# 6-digit-board.net
KiCad netlist of a schematic drawn in EAGLE
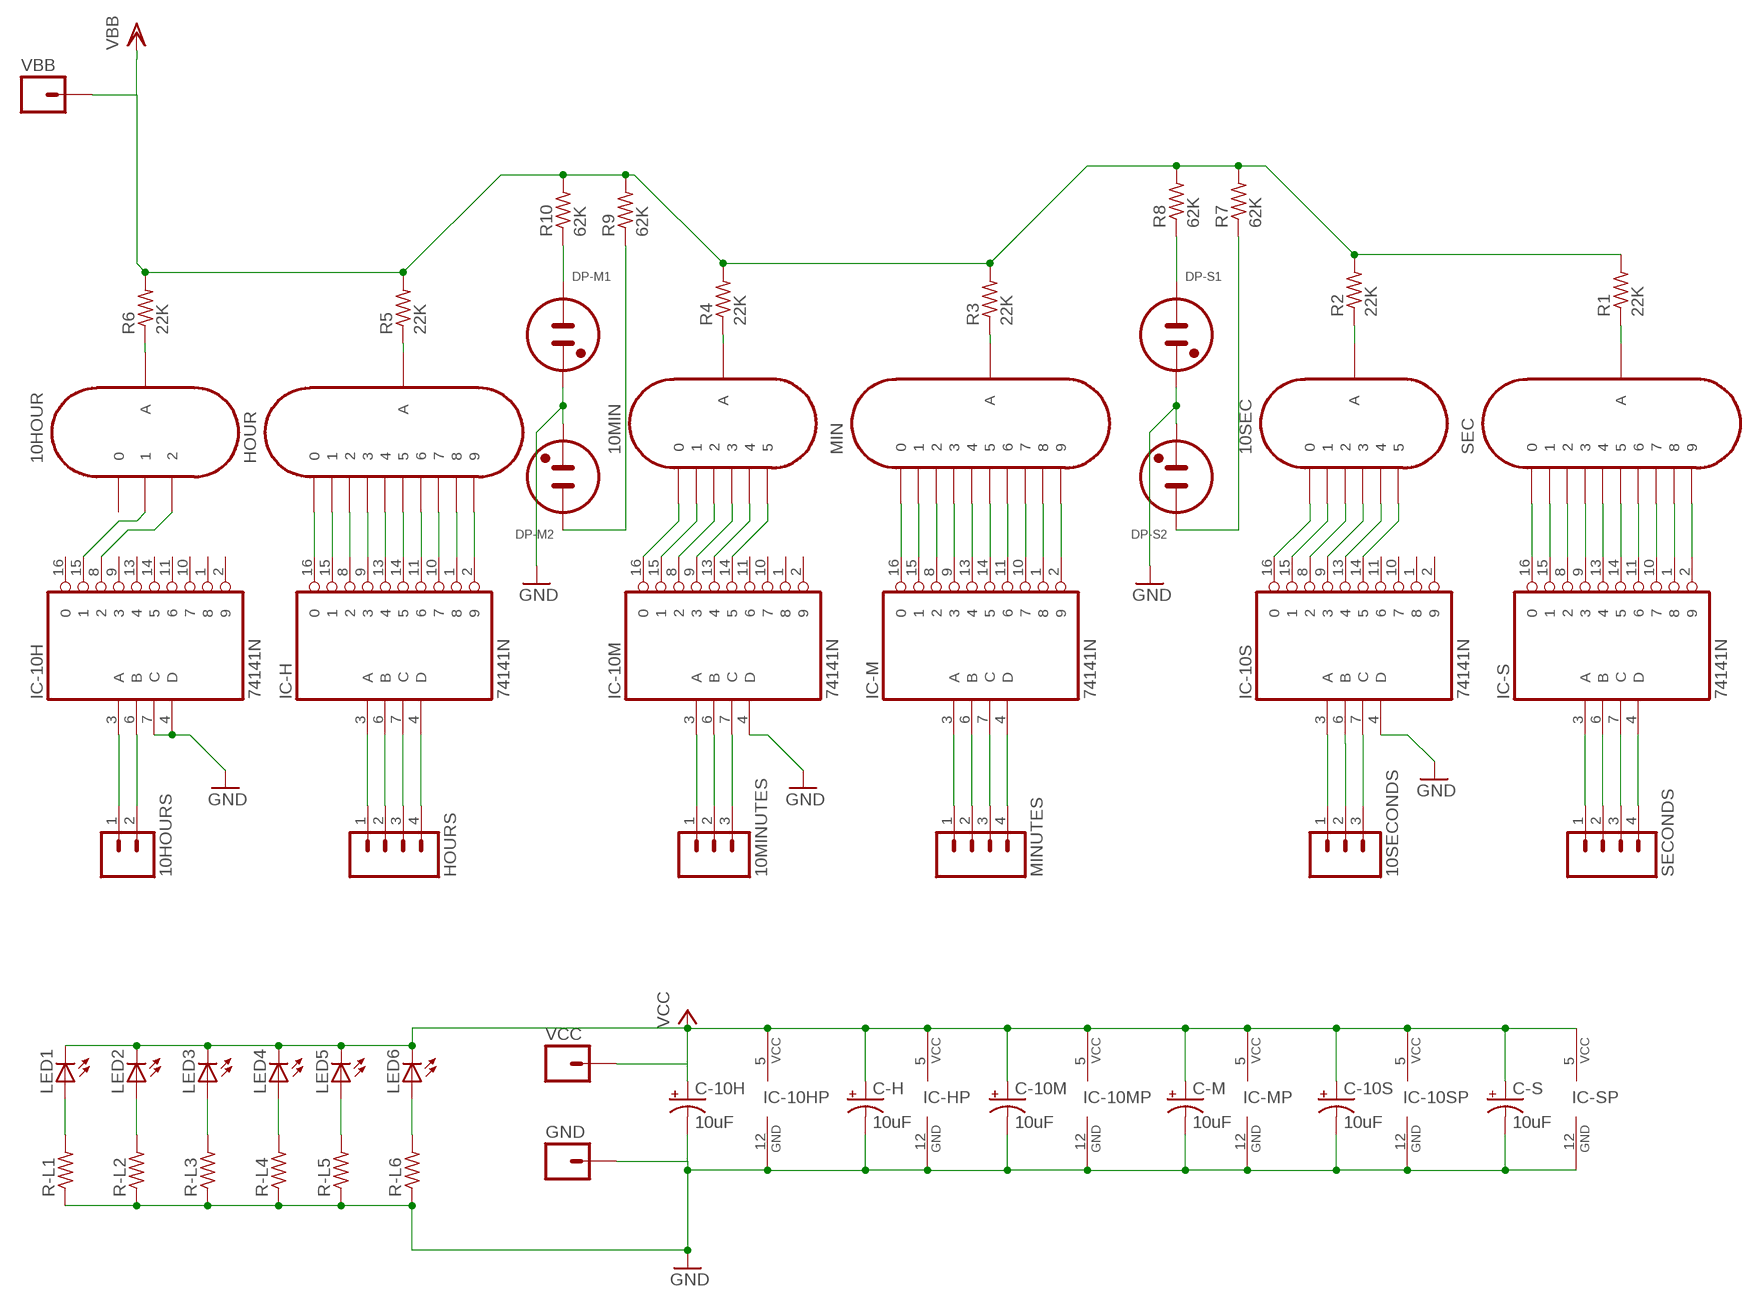
[diagram p0: schematic, sheet 1]

(export (version "E")
  (design (tool "Eeschema 10.0.6"))
  (components
    (comp (ref "10HOUR")
      (value "IN-12_2DIGIT")
      (footprint "eagle-import:IN-12_2DIGIT")
      (libsource (lib "eagle-import") (part "IN-12_2DIGIT"))
    )
    (comp (ref "10HOURS")
      (value "M02PTH3")
      (footprint "eagle-import:1X02_LONGPADS")
      (libsource (lib "eagle-import") (part "M02PTH3"))
    )
    (comp (ref "10MIN")
      (value "IN-12_6DIGIT")
      (footprint "eagle-import:IN-12_6DIGIT")
      (libsource (lib "eagle-import") (part "IN-12_6DIGIT"))
    )
    (comp (ref "10MINUTES")
      (value "M03LONGPADS")
      (footprint "eagle-import:1X03_LONGPADS")
      (libsource (lib "eagle-import") (part "M03LONGPADS"))
    )
    (comp (ref "10SEC")
      (value "IN-12_6DIGIT")
      (footprint "eagle-import:IN-12_6DIGIT")
      (libsource (lib "eagle-import") (part "IN-12_6DIGIT"))
    )
    (comp (ref "10SECONDS")
      (value "M03LONGPADS")
      (footprint "eagle-import:1X03_LONGPADS")
      (libsource (lib "eagle-import") (part "M03LONGPADS"))
    )
    (comp (ref "C-10H")
      (value "10uF")
      (footprint "eagle-import:B_3528-21R")
      (libsource (lib "eagle-import") (part "CAPACITOR_POLB/3528-21R"))
    )
    (comp (ref "C-10M")
      (value "10uF")
      (footprint "eagle-import:B_3528-21R")
      (libsource (lib "eagle-import") (part "CAPACITOR_POLB/3528-21R"))
    )
    (comp (ref "C-10S")
      (value "10uF")
      (footprint "eagle-import:B_3528-21R")
      (libsource (lib "eagle-import") (part "CAPACITOR_POLB/3528-21R"))
    )
    (comp (ref "C-H")
      (value "10uF")
      (footprint "eagle-import:B_3528-21R")
      (libsource (lib "eagle-import") (part "CAPACITOR_POLB/3528-21R"))
    )
    (comp (ref "C-M")
      (value "10uF")
      (footprint "eagle-import:B_3528-21R")
      (libsource (lib "eagle-import") (part "CAPACITOR_POLB/3528-21R"))
    )
    (comp (ref "C-S")
      (value "10uF")
      (footprint "eagle-import:B_3528-21R")
      (libsource (lib "eagle-import") (part "CAPACITOR_POLB/3528-21R"))
    )
    (comp (ref "DP-M1")
      (value "INS-1")
      (footprint "eagle-import:INS-1")
      (libsource (lib "eagle-import") (part "INS-1"))
    )
    (comp (ref "DP-M2")
      (value "INS-1")
      (footprint "eagle-import:INS-1")
      (libsource (lib "eagle-import") (part "INS-1"))
    )
    (comp (ref "DP-S1")
      (value "INS-1")
      (footprint "eagle-import:INS-1")
      (libsource (lib "eagle-import") (part "INS-1"))
    )
    (comp (ref "DP-S2")
      (value "INS-1")
      (footprint "eagle-import:INS-1")
      (libsource (lib "eagle-import") (part "INS-1"))
    )
    (comp (ref "GND")
      (value "M01PTH")
      (footprint "eagle-import:1X01")
      (libsource (lib "eagle-import") (part "M01PTH"))
    )
    (comp (ref "HOUR")
      (value "IN-12A-NO_DP")
      (footprint "eagle-import:IN-12_NO-DP")
      (libsource (lib "eagle-import") (part "IN-12A-NO_DP"))
    )
    (comp (ref "HOURS")
      (value "M04LONGPADS")
      (footprint "eagle-import:1X04_LONGPADS")
      (libsource (lib "eagle-import") (part "M04LONGPADS"))
    )
    (comp (ref "IC-10H")
      (value "74141N")
      (footprint "eagle-import:DIL16")
      (libsource (lib "eagle-import") (part "74141N"))
    )
    (comp (ref "IC-10M")
      (value "74141N")
      (footprint "eagle-import:DIL16")
      (libsource (lib "eagle-import") (part "74141N"))
    )
    (comp (ref "IC-10S")
      (value "74141N")
      (footprint "eagle-import:DIL16")
      (libsource (lib "eagle-import") (part "74141N"))
    )
    (comp (ref "IC-H")
      (value "74141N")
      (footprint "eagle-import:DIL16")
      (libsource (lib "eagle-import") (part "74141N"))
    )
    (comp (ref "IC-M")
      (value "74141N")
      (footprint "eagle-import:DIL16")
      (libsource (lib "eagle-import") (part "74141N"))
    )
    (comp (ref "IC-S")
      (value "74141N")
      (footprint "eagle-import:DIL16")
      (libsource (lib "eagle-import") (part "74141N"))
    )
    (comp (ref "LED1")
      (value "LED1210")
      (footprint "eagle-import:LED1210")
      (libsource (lib "eagle-import") (part "LED1210"))
    )
    (comp (ref "LED2")
      (value "LED1210")
      (footprint "eagle-import:LED1210")
      (libsource (lib "eagle-import") (part "LED1210"))
    )
    (comp (ref "LED3")
      (value "LED1210")
      (footprint "eagle-import:LED1210")
      (libsource (lib "eagle-import") (part "LED1210"))
    )
    (comp (ref "LED4")
      (value "LED1210")
      (footprint "eagle-import:LED1210")
      (libsource (lib "eagle-import") (part "LED1210"))
    )
    (comp (ref "LED5")
      (value "LED1210")
      (footprint "eagle-import:LED1210")
      (libsource (lib "eagle-import") (part "LED1210"))
    )
    (comp (ref "LED6")
      (value "LED1210")
      (footprint "eagle-import:LED1210")
      (libsource (lib "eagle-import") (part "LED1210"))
    )
    (comp (ref "MIN")
      (value "IN-12A-NO_DP")
      (footprint "eagle-import:IN-12_NO-DP")
      (libsource (lib "eagle-import") (part "IN-12A-NO_DP"))
    )
    (comp (ref "MINUTES")
      (value "M04LONGPADS")
      (footprint "eagle-import:1X04_LONGPADS")
      (libsource (lib "eagle-import") (part "M04LONGPADS"))
    )
    (comp (ref "R-L1")
      (value "RESISTORR1206")
      (footprint "eagle-import:R1206")
      (libsource (lib "eagle-import") (part "RESISTORR1206"))
    )
    (comp (ref "R-L2")
      (value "RESISTORR1206")
      (footprint "eagle-import:R1206")
      (libsource (lib "eagle-import") (part "RESISTORR1206"))
    )
    (comp (ref "R-L3")
      (value "RESISTORR1206")
      (footprint "eagle-import:R1206")
      (libsource (lib "eagle-import") (part "RESISTORR1206"))
    )
    (comp (ref "R-L4")
      (value "RESISTORR1206")
      (footprint "eagle-import:R1206")
      (libsource (lib "eagle-import") (part "RESISTORR1206"))
    )
    (comp (ref "R-L5")
      (value "RESISTORR1206")
      (footprint "eagle-import:R1206")
      (libsource (lib "eagle-import") (part "RESISTORR1206"))
    )
    (comp (ref "R-L6")
      (value "RESISTORR1206")
      (footprint "eagle-import:R1206")
      (libsource (lib "eagle-import") (part "RESISTORR1206"))
    )
    (comp (ref "R1")
      (value "22K")
      (footprint "eagle-import:0207_10")
      (libsource (lib "eagle-import") (part "RESISTOR0207/10"))
    )
    (comp (ref "R2")
      (value "22K")
      (footprint "eagle-import:0207_10")
      (libsource (lib "eagle-import") (part "RESISTOR0207/10"))
    )
    (comp (ref "R3")
      (value "22K")
      (footprint "eagle-import:0207_10")
      (libsource (lib "eagle-import") (part "RESISTOR0207/10"))
    )
    (comp (ref "R4")
      (value "22K")
      (footprint "eagle-import:0207_10")
      (libsource (lib "eagle-import") (part "RESISTOR0207/10"))
    )
    (comp (ref "R5")
      (value "22K")
      (footprint "eagle-import:0207_10")
      (libsource (lib "eagle-import") (part "RESISTOR0207/10"))
    )
    (comp (ref "R6")
      (value "22K")
      (footprint "eagle-import:0207_10")
      (libsource (lib "eagle-import") (part "RESISTOR0207/10"))
    )
    (comp (ref "R7")
      (value "62K")
      (footprint "eagle-import:0207_10")
      (libsource (lib "eagle-import") (part "RESISTOR0207/10"))
    )
    (comp (ref "R8")
      (value "62K")
      (footprint "eagle-import:0207_10")
      (libsource (lib "eagle-import") (part "RESISTOR0207/10"))
    )
    (comp (ref "R9")
      (value "62K")
      (footprint "eagle-import:0207_10")
      (libsource (lib "eagle-import") (part "RESISTOR0207/10"))
    )
    (comp (ref "R10")
      (value "62K")
      (footprint "eagle-import:0207_10")
      (libsource (lib "eagle-import") (part "RESISTOR0207/10"))
    )
    (comp (ref "SEC")
      (value "IN-12A-NO_DP")
      (footprint "eagle-import:IN-12_NO-DP")
      (libsource (lib "eagle-import") (part "IN-12A-NO_DP"))
    )
    (comp (ref "SECONDS")
      (value "M04LONGPADS")
      (footprint "eagle-import:1X04_LONGPADS")
      (libsource (lib "eagle-import") (part "M04LONGPADS"))
    )
    (comp (ref "VBB")
      (value "M01PTH")
      (footprint "eagle-import:1X01")
      (libsource (lib "eagle-import") (part "M01PTH"))
    )
    (comp (ref "VCC")
      (value "M01PTH")
      (footprint "eagle-import:1X01")
      (libsource (lib "eagle-import") (part "M01PTH"))
    )
  )
  (nets
    (net (code "1") (name "GND") (class "Default")
      (node (ref "C-10H") (pin "-") (pinfunction "-_-") (pintype "passive"))
      (node (ref "C-10M") (pin "-") (pinfunction "-_-") (pintype "passive"))
      (node (ref "C-10S") (pin "-") (pinfunction "-_-") (pintype "passive"))
      (node (ref "C-H") (pin "-") (pinfunction "-_-") (pintype "passive"))
      (node (ref "C-M") (pin "-") (pinfunction "-_-") (pintype "passive"))
      (node (ref "C-S") (pin "-") (pinfunction "-_-") (pintype "passive"))
      (node (ref "DP-M1") (pin "K") (pinfunction "K_K") (pintype "passive"))
      (node (ref "DP-M2") (pin "K") (pinfunction "K_K") (pintype "passive"))
      (node (ref "DP-S1") (pin "K") (pinfunction "K_K") (pintype "passive"))
      (node (ref "DP-S2") (pin "K") (pinfunction "K_K") (pintype "passive"))
      (node (ref "GND") (pin "1") (pinfunction "1_1") (pintype "passive"))
      (node (ref "IC-10H") (pin "12") (pinfunction "GND_12") (pintype "power_in"))
      (node (ref "IC-10H") (pin "4") (pinfunction "D_4") (pintype "input"))
      (node (ref "IC-10H") (pin "7") (pinfunction "C_7") (pintype "input"))
      (node (ref "IC-10M") (pin "12") (pinfunction "GND_12") (pintype "power_in"))
      (node (ref "IC-10M") (pin "4") (pinfunction "D_4") (pintype "input"))
      (node (ref "IC-10S") (pin "12") (pinfunction "GND_12") (pintype "power_in"))
      (node (ref "IC-10S") (pin "4") (pinfunction "D_4") (pintype "input"))
      (node (ref "IC-H") (pin "12") (pinfunction "GND_12") (pintype "power_in"))
      (node (ref "IC-M") (pin "12") (pinfunction "GND_12") (pintype "power_in"))
      (node (ref "IC-S") (pin "12") (pinfunction "GND_12") (pintype "power_in"))
      (node (ref "R-L1") (pin "1") (pinfunction "1_1") (pintype "passive"))
      (node (ref "R-L2") (pin "1") (pinfunction "1_1") (pintype "passive"))
      (node (ref "R-L3") (pin "1") (pinfunction "1_1") (pintype "passive"))
      (node (ref "R-L4") (pin "1") (pinfunction "1_1") (pintype "passive"))
      (node (ref "R-L5") (pin "1") (pinfunction "1_1") (pintype "passive"))
      (node (ref "R-L6") (pin "1") (pinfunction "1_1") (pintype "passive"))
    )
    (net (code "2") (name "Net-(10HOUR-PadA)") (class "Default")
      (node (ref "10HOUR") (pin "A") (pinfunction "A_A") (pintype "bidirectional"))
      (node (ref "R6") (pin "1") (pinfunction "1_1") (pintype "passive"))
    )
    (net (code "3") (name "Net-(10MIN-PadA)") (class "Default")
      (node (ref "10MIN") (pin "A") (pinfunction "A_A") (pintype "bidirectional"))
      (node (ref "R4") (pin "1") (pinfunction "1_1") (pintype "passive"))
    )
    (net (code "4") (name "Net-(10SEC-PadA)") (class "Default")
      (node (ref "10SEC") (pin "A") (pinfunction "A_A") (pintype "bidirectional"))
      (node (ref "R2") (pin "1") (pinfunction "1_1") (pintype "passive"))
    )
    (net (code "5") (name "Net-(DP-M1-PadA)") (class "Default")
      (node (ref "DP-M1") (pin "A") (pinfunction "A_A") (pintype "passive"))
      (node (ref "R10") (pin "1") (pinfunction "1_1") (pintype "passive"))
    )
    (net (code "6") (name "Net-(DP-M2-PadA)") (class "Default")
      (node (ref "DP-M2") (pin "A") (pinfunction "A_A") (pintype "passive"))
      (node (ref "R9") (pin "1") (pinfunction "1_1") (pintype "passive"))
    )
    (net (code "7") (name "Net-(DP-S1-PadA)") (class "Default")
      (node (ref "DP-S1") (pin "A") (pinfunction "A_A") (pintype "passive"))
      (node (ref "R8") (pin "1") (pinfunction "1_1") (pintype "passive"))
    )
    (net (code "8") (name "Net-(DP-S2-PadA)") (class "Default")
      (node (ref "DP-S2") (pin "A") (pinfunction "A_A") (pintype "passive"))
      (node (ref "R7") (pin "1") (pinfunction "1_1") (pintype "passive"))
    )
    (net (code "9") (name "Net-(HOUR-PadA)") (class "Default")
      (node (ref "HOUR") (pin "A") (pinfunction "A_A") (pintype "bidirectional"))
      (node (ref "R5") (pin "1") (pinfunction "1_1") (pintype "passive"))
    )
    (net (code "10") (name "Net-(IC-10HA-1)") (class "Default")
      (node (ref "10HOUR") (pin "1") (pinfunction "1_1") (pintype "bidirectional"))
      (node (ref "IC-10H") (pin "15") (pinfunction "1_15") (pintype "open_collector"))
    )
    (net (code "11") (name "Net-(IC-10HA-2)") (class "Default")
      (node (ref "10HOUR") (pin "2") (pinfunction "2_2") (pintype "bidirectional"))
      (node (ref "IC-10H") (pin "8") (pinfunction "2_8") (pintype "open_collector"))
    )
    (net (code "12") (name "Net-(IC-10HA-A)") (class "Default")
      (node (ref "10HOURS") (pin "1") (pinfunction "1_1") (pintype "passive"))
      (node (ref "IC-10H") (pin "3") (pinfunction "A_3") (pintype "input"))
    )
    (net (code "13") (name "Net-(IC-10HA-B)") (class "Default")
      (node (ref "10HOURS") (pin "2") (pinfunction "2_2") (pintype "passive"))
      (node (ref "IC-10H") (pin "6") (pinfunction "B_6") (pintype "input"))
    )
    (net (code "14") (name "Net-(IC-10MA-0)") (class "Default")
      (node (ref "10MIN") (pin "0") (pinfunction "0_0") (pintype "bidirectional"))
      (node (ref "IC-10M") (pin "16") (pinfunction "0_16") (pintype "open_collector"))
    )
    (net (code "15") (name "Net-(IC-10MA-1)") (class "Default")
      (node (ref "10MIN") (pin "1") (pinfunction "1_1") (pintype "bidirectional"))
      (node (ref "IC-10M") (pin "15") (pinfunction "1_15") (pintype "open_collector"))
    )
    (net (code "16") (name "Net-(IC-10MA-2)") (class "Default")
      (node (ref "10MIN") (pin "2") (pinfunction "2_2") (pintype "bidirectional"))
      (node (ref "IC-10M") (pin "8") (pinfunction "2_8") (pintype "open_collector"))
    )
    (net (code "17") (name "Net-(IC-10MA-3)") (class "Default")
      (node (ref "10MIN") (pin "3") (pinfunction "3_3") (pintype "bidirectional"))
      (node (ref "IC-10M") (pin "9") (pinfunction "3_9") (pintype "open_collector"))
    )
    (net (code "18") (name "Net-(IC-10MA-4)") (class "Default")
      (node (ref "10MIN") (pin "4") (pinfunction "4_4") (pintype "bidirectional"))
      (node (ref "IC-10M") (pin "13") (pinfunction "4_13") (pintype "open_collector"))
    )
    (net (code "19") (name "Net-(IC-10MA-5)") (class "Default")
      (node (ref "10MIN") (pin "5") (pinfunction "5_5") (pintype "bidirectional"))
      (node (ref "IC-10M") (pin "14") (pinfunction "5_14") (pintype "open_collector"))
    )
    (net (code "20") (name "Net-(IC-10MA-A)") (class "Default")
      (node (ref "10MINUTES") (pin "1") (pinfunction "1_1") (pintype "passive"))
      (node (ref "IC-10M") (pin "3") (pinfunction "A_3") (pintype "input"))
    )
    (net (code "21") (name "Net-(IC-10MA-B)") (class "Default")
      (node (ref "10MINUTES") (pin "2") (pinfunction "2_2") (pintype "passive"))
      (node (ref "IC-10M") (pin "6") (pinfunction "B_6") (pintype "input"))
    )
    (net (code "22") (name "Net-(IC-10MA-C)") (class "Default")
      (node (ref "10MINUTES") (pin "3") (pinfunction "3_3") (pintype "passive"))
      (node (ref "IC-10M") (pin "7") (pinfunction "C_7") (pintype "input"))
    )
    (net (code "23") (name "Net-(IC-10SA-0)") (class "Default")
      (node (ref "10SEC") (pin "0") (pinfunction "0_0") (pintype "bidirectional"))
      (node (ref "IC-10S") (pin "16") (pinfunction "0_16") (pintype "open_collector"))
    )
    (net (code "24") (name "Net-(IC-10SA-1)") (class "Default")
      (node (ref "10SEC") (pin "1") (pinfunction "1_1") (pintype "bidirectional"))
      (node (ref "IC-10S") (pin "15") (pinfunction "1_15") (pintype "open_collector"))
    )
    (net (code "25") (name "Net-(IC-10SA-2)") (class "Default")
      (node (ref "10SEC") (pin "2") (pinfunction "2_2") (pintype "bidirectional"))
      (node (ref "IC-10S") (pin "8") (pinfunction "2_8") (pintype "open_collector"))
    )
    (net (code "26") (name "Net-(IC-10SA-3)") (class "Default")
      (node (ref "10SEC") (pin "3") (pinfunction "3_3") (pintype "bidirectional"))
      (node (ref "IC-10S") (pin "9") (pinfunction "3_9") (pintype "open_collector"))
    )
    (net (code "27") (name "Net-(IC-10SA-4)") (class "Default")
      (node (ref "10SEC") (pin "4") (pinfunction "4_4") (pintype "bidirectional"))
      (node (ref "IC-10S") (pin "13") (pinfunction "4_13") (pintype "open_collector"))
    )
    (net (code "28") (name "Net-(IC-10SA-5)") (class "Default")
      (node (ref "10SEC") (pin "5") (pinfunction "5_5") (pintype "bidirectional"))
      (node (ref "IC-10S") (pin "14") (pinfunction "5_14") (pintype "open_collector"))
    )
    (net (code "29") (name "Net-(IC-10SA-A)") (class "Default")
      (node (ref "10SECONDS") (pin "1") (pinfunction "1_1") (pintype "passive"))
      (node (ref "IC-10S") (pin "3") (pinfunction "A_3") (pintype "input"))
    )
    (net (code "30") (name "Net-(IC-10SA-B)") (class "Default")
      (node (ref "10SECONDS") (pin "2") (pinfunction "2_2") (pintype "passive"))
      (node (ref "IC-10S") (pin "6") (pinfunction "B_6") (pintype "input"))
    )
    (net (code "31") (name "Net-(IC-10SA-C)") (class "Default")
      (node (ref "10SECONDS") (pin "3") (pinfunction "3_3") (pintype "passive"))
      (node (ref "IC-10S") (pin "7") (pinfunction "C_7") (pintype "input"))
    )
    (net (code "32") (name "Net-(IC-HA-0)") (class "Default")
      (node (ref "HOUR") (pin "0") (pinfunction "0_0") (pintype "bidirectional"))
      (node (ref "IC-H") (pin "16") (pinfunction "0_16") (pintype "open_collector"))
    )
    (net (code "33") (name "Net-(IC-HA-1)") (class "Default")
      (node (ref "HOUR") (pin "1") (pinfunction "1_1") (pintype "bidirectional"))
      (node (ref "IC-H") (pin "15") (pinfunction "1_15") (pintype "open_collector"))
    )
    (net (code "34") (name "Net-(IC-HA-2)") (class "Default")
      (node (ref "HOUR") (pin "2") (pinfunction "2_2") (pintype "bidirectional"))
      (node (ref "IC-H") (pin "8") (pinfunction "2_8") (pintype "open_collector"))
    )
    (net (code "35") (name "Net-(IC-HA-3)") (class "Default")
      (node (ref "HOUR") (pin "3") (pinfunction "3_3") (pintype "bidirectional"))
      (node (ref "IC-H") (pin "9") (pinfunction "3_9") (pintype "open_collector"))
    )
    (net (code "36") (name "Net-(IC-HA-4)") (class "Default")
      (node (ref "HOUR") (pin "4") (pinfunction "4_4") (pintype "bidirectional"))
      (node (ref "IC-H") (pin "13") (pinfunction "4_13") (pintype "open_collector"))
    )
    (net (code "37") (name "Net-(IC-HA-5)") (class "Default")
      (node (ref "HOUR") (pin "5") (pinfunction "5_5") (pintype "bidirectional"))
      (node (ref "IC-H") (pin "14") (pinfunction "5_14") (pintype "open_collector"))
    )
    (net (code "38") (name "Net-(IC-HA-6)") (class "Default")
      (node (ref "HOUR") (pin "6") (pinfunction "6_6") (pintype "bidirectional"))
      (node (ref "IC-H") (pin "11") (pinfunction "6_11") (pintype "open_collector"))
    )
    (net (code "39") (name "Net-(IC-HA-7)") (class "Default")
      (node (ref "HOUR") (pin "7") (pinfunction "7_7") (pintype "bidirectional"))
      (node (ref "IC-H") (pin "10") (pinfunction "7_10") (pintype "open_collector"))
    )
    (net (code "40") (name "Net-(IC-HA-8)") (class "Default")
      (node (ref "HOUR") (pin "8") (pinfunction "8_8") (pintype "bidirectional"))
      (node (ref "IC-H") (pin "1") (pinfunction "8_1") (pintype "open_collector"))
    )
    (net (code "41") (name "Net-(IC-HA-9)") (class "Default")
      (node (ref "HOUR") (pin "9") (pinfunction "9_9") (pintype "bidirectional"))
      (node (ref "IC-H") (pin "2") (pinfunction "9_2") (pintype "open_collector"))
    )
    (net (code "42") (name "Net-(IC-HA-A)") (class "Default")
      (node (ref "HOURS") (pin "1") (pinfunction "1_1") (pintype "passive"))
      (node (ref "IC-H") (pin "3") (pinfunction "A_3") (pintype "input"))
    )
    (net (code "43") (name "Net-(IC-HA-B)") (class "Default")
      (node (ref "HOURS") (pin "2") (pinfunction "2_2") (pintype "passive"))
      (node (ref "IC-H") (pin "6") (pinfunction "B_6") (pintype "input"))
    )
    (net (code "44") (name "Net-(IC-HA-C)") (class "Default")
      (node (ref "HOURS") (pin "3") (pinfunction "3_3") (pintype "passive"))
      (node (ref "IC-H") (pin "7") (pinfunction "C_7") (pintype "input"))
    )
    (net (code "45") (name "Net-(IC-HA-D)") (class "Default")
      (node (ref "HOURS") (pin "4") (pinfunction "4_4") (pintype "passive"))
      (node (ref "IC-H") (pin "4") (pinfunction "D_4") (pintype "input"))
    )
    (net (code "46") (name "Net-(IC-MA-0)") (class "Default")
      (node (ref "IC-M") (pin "16") (pinfunction "0_16") (pintype "open_collector"))
      (node (ref "MIN") (pin "0") (pinfunction "0_0") (pintype "bidirectional"))
    )
    (net (code "47") (name "Net-(IC-MA-1)") (class "Default")
      (node (ref "IC-M") (pin "15") (pinfunction "1_15") (pintype "open_collector"))
      (node (ref "MIN") (pin "1") (pinfunction "1_1") (pintype "bidirectional"))
    )
    (net (code "48") (name "Net-(IC-MA-2)") (class "Default")
      (node (ref "IC-M") (pin "8") (pinfunction "2_8") (pintype "open_collector"))
      (node (ref "MIN") (pin "2") (pinfunction "2_2") (pintype "bidirectional"))
    )
    (net (code "49") (name "Net-(IC-MA-3)") (class "Default")
      (node (ref "IC-M") (pin "9") (pinfunction "3_9") (pintype "open_collector"))
      (node (ref "MIN") (pin "3") (pinfunction "3_3") (pintype "bidirectional"))
    )
    (net (code "50") (name "Net-(IC-MA-4)") (class "Default")
      (node (ref "IC-M") (pin "13") (pinfunction "4_13") (pintype "open_collector"))
      (node (ref "MIN") (pin "4") (pinfunction "4_4") (pintype "bidirectional"))
    )
    (net (code "51") (name "Net-(IC-MA-5)") (class "Default")
      (node (ref "IC-M") (pin "14") (pinfunction "5_14") (pintype "open_collector"))
      (node (ref "MIN") (pin "5") (pinfunction "5_5") (pintype "bidirectional"))
    )
    (net (code "52") (name "Net-(IC-MA-6)") (class "Default")
      (node (ref "IC-M") (pin "11") (pinfunction "6_11") (pintype "open_collector"))
      (node (ref "MIN") (pin "6") (pinfunction "6_6") (pintype "bidirectional"))
    )
    (net (code "53") (name "Net-(IC-MA-7)") (class "Default")
      (node (ref "IC-M") (pin "10") (pinfunction "7_10") (pintype "open_collector"))
      (node (ref "MIN") (pin "7") (pinfunction "7_7") (pintype "bidirectional"))
    )
    (net (code "54") (name "Net-(IC-MA-8)") (class "Default")
      (node (ref "IC-M") (pin "1") (pinfunction "8_1") (pintype "open_collector"))
      (node (ref "MIN") (pin "8") (pinfunction "8_8") (pintype "bidirectional"))
    )
    (net (code "55") (name "Net-(IC-MA-9)") (class "Default")
      (node (ref "IC-M") (pin "2") (pinfunction "9_2") (pintype "open_collector"))
      (node (ref "MIN") (pin "9") (pinfunction "9_9") (pintype "bidirectional"))
    )
    (net (code "56") (name "Net-(IC-MA-A)") (class "Default")
      (node (ref "IC-M") (pin "3") (pinfunction "A_3") (pintype "input"))
      (node (ref "MINUTES") (pin "1") (pinfunction "1_1") (pintype "passive"))
    )
    (net (code "57") (name "Net-(IC-MA-B)") (class "Default")
      (node (ref "IC-M") (pin "6") (pinfunction "B_6") (pintype "input"))
      (node (ref "MINUTES") (pin "2") (pinfunction "2_2") (pintype "passive"))
    )
    (net (code "58") (name "Net-(IC-MA-C)") (class "Default")
      (node (ref "IC-M") (pin "7") (pinfunction "C_7") (pintype "input"))
      (node (ref "MINUTES") (pin "3") (pinfunction "3_3") (pintype "passive"))
    )
    (net (code "59") (name "Net-(IC-MA-D)") (class "Default")
      (node (ref "IC-M") (pin "4") (pinfunction "D_4") (pintype "input"))
      (node (ref "MINUTES") (pin "4") (pinfunction "4_4") (pintype "passive"))
    )
    (net (code "60") (name "Net-(IC-SA-0)") (class "Default")
      (node (ref "IC-S") (pin "16") (pinfunction "0_16") (pintype "open_collector"))
      (node (ref "SEC") (pin "0") (pinfunction "0_0") (pintype "bidirectional"))
    )
    (net (code "61") (name "Net-(IC-SA-1)") (class "Default")
      (node (ref "IC-S") (pin "15") (pinfunction "1_15") (pintype "open_collector"))
      (node (ref "SEC") (pin "1") (pinfunction "1_1") (pintype "bidirectional"))
    )
    (net (code "62") (name "Net-(IC-SA-2)") (class "Default")
      (node (ref "IC-S") (pin "8") (pinfunction "2_8") (pintype "open_collector"))
      (node (ref "SEC") (pin "2") (pinfunction "2_2") (pintype "bidirectional"))
    )
    (net (code "63") (name "Net-(IC-SA-3)") (class "Default")
      (node (ref "IC-S") (pin "9") (pinfunction "3_9") (pintype "open_collector"))
      (node (ref "SEC") (pin "3") (pinfunction "3_3") (pintype "bidirectional"))
    )
    (net (code "64") (name "Net-(IC-SA-4)") (class "Default")
      (node (ref "IC-S") (pin "13") (pinfunction "4_13") (pintype "open_collector"))
      (node (ref "SEC") (pin "4") (pinfunction "4_4") (pintype "bidirectional"))
    )
    (net (code "65") (name "Net-(IC-SA-5)") (class "Default")
      (node (ref "IC-S") (pin "14") (pinfunction "5_14") (pintype "open_collector"))
      (node (ref "SEC") (pin "5") (pinfunction "5_5") (pintype "bidirectional"))
    )
    (net (code "66") (name "Net-(IC-SA-6)") (class "Default")
      (node (ref "IC-S") (pin "11") (pinfunction "6_11") (pintype "open_collector"))
      (node (ref "SEC") (pin "6") (pinfunction "6_6") (pintype "bidirectional"))
    )
    (net (code "67") (name "Net-(IC-SA-7)") (class "Default")
      (node (ref "IC-S") (pin "10") (pinfunction "7_10") (pintype "open_collector"))
      (node (ref "SEC") (pin "7") (pinfunction "7_7") (pintype "bidirectional"))
    )
    (net (code "68") (name "Net-(IC-SA-8)") (class "Default")
      (node (ref "IC-S") (pin "1") (pinfunction "8_1") (pintype "open_collector"))
      (node (ref "SEC") (pin "8") (pinfunction "8_8") (pintype "bidirectional"))
    )
    (net (code "69") (name "Net-(IC-SA-9)") (class "Default")
      (node (ref "IC-S") (pin "2") (pinfunction "9_2") (pintype "open_collector"))
      (node (ref "SEC") (pin "9") (pinfunction "9_9") (pintype "bidirectional"))
    )
    (net (code "70") (name "Net-(IC-SA-A)") (class "Default")
      (node (ref "IC-S") (pin "3") (pinfunction "A_3") (pintype "input"))
      (node (ref "SECONDS") (pin "1") (pinfunction "1_1") (pintype "passive"))
    )
    (net (code "71") (name "Net-(IC-SA-B)") (class "Default")
      (node (ref "IC-S") (pin "6") (pinfunction "B_6") (pintype "input"))
      (node (ref "SECONDS") (pin "2") (pinfunction "2_2") (pintype "passive"))
    )
    (net (code "72") (name "Net-(IC-SA-C)") (class "Default")
      (node (ref "IC-S") (pin "7") (pinfunction "C_7") (pintype "input"))
      (node (ref "SECONDS") (pin "3") (pinfunction "3_3") (pintype "passive"))
    )
    (net (code "73") (name "Net-(IC-SA-D)") (class "Default")
      (node (ref "IC-S") (pin "4") (pinfunction "D_4") (pintype "input"))
      (node (ref "SECONDS") (pin "4") (pinfunction "4_4") (pintype "passive"))
    )
    (net (code "74") (name "Net-(LED1-PadA)") (class "Default")
      (node (ref "LED1") (pin "A") (pinfunction "A_A") (pintype "passive"))
      (node (ref "R-L1") (pin "2") (pinfunction "2_2") (pintype "passive"))
    )
    (net (code "75") (name "Net-(LED2-PadA)") (class "Default")
      (node (ref "LED2") (pin "A") (pinfunction "A_A") (pintype "passive"))
      (node (ref "R-L2") (pin "2") (pinfunction "2_2") (pintype "passive"))
    )
    (net (code "76") (name "Net-(LED3-PadA)") (class "Default")
      (node (ref "LED3") (pin "A") (pinfunction "A_A") (pintype "passive"))
      (node (ref "R-L3") (pin "2") (pinfunction "2_2") (pintype "passive"))
    )
    (net (code "77") (name "Net-(LED4-PadA)") (class "Default")
      (node (ref "LED4") (pin "A") (pinfunction "A_A") (pintype "passive"))
      (node (ref "R-L4") (pin "2") (pinfunction "2_2") (pintype "passive"))
    )
    (net (code "78") (name "Net-(LED5-PadA)") (class "Default")
      (node (ref "LED5") (pin "A") (pinfunction "A_A") (pintype "passive"))
      (node (ref "R-L5") (pin "2") (pinfunction "2_2") (pintype "passive"))
    )
    (net (code "79") (name "Net-(LED6-PadA)") (class "Default")
      (node (ref "LED6") (pin "A") (pinfunction "A_A") (pintype "passive"))
      (node (ref "R-L6") (pin "2") (pinfunction "2_2") (pintype "passive"))
    )
    (net (code "80") (name "Net-(MIN-PadA)") (class "Default")
      (node (ref "MIN") (pin "A") (pinfunction "A_A") (pintype "bidirectional"))
      (node (ref "R3") (pin "1") (pinfunction "1_1") (pintype "passive"))
    )
    (net (code "81") (name "Net-(R1-Pad1)") (class "Default")
      (node (ref "R1") (pin "1") (pinfunction "1_1") (pintype "passive"))
      (node (ref "SEC") (pin "A") (pinfunction "A_A") (pintype "bidirectional"))
    )
    (net (code "82") (name "VBB") (class "Default")
      (node (ref "R1") (pin "2") (pinfunction "2_2") (pintype "passive"))
      (node (ref "R10") (pin "2") (pinfunction "2_2") (pintype "passive"))
      (node (ref "R2") (pin "2") (pinfunction "2_2") (pintype "passive"))
      (node (ref "R3") (pin "2") (pinfunction "2_2") (pintype "passive"))
      (node (ref "R4") (pin "2") (pinfunction "2_2") (pintype "passive"))
      (node (ref "R5") (pin "2") (pinfunction "2_2") (pintype "passive"))
      (node (ref "R6") (pin "2") (pinfunction "2_2") (pintype "passive"))
      (node (ref "R7") (pin "2") (pinfunction "2_2") (pintype "passive"))
      (node (ref "R8") (pin "2") (pinfunction "2_2") (pintype "passive"))
      (node (ref "R9") (pin "2") (pinfunction "2_2") (pintype "passive"))
      (node (ref "VBB") (pin "1") (pinfunction "1_1") (pintype "passive"))
    )
    (net (code "83") (name "VCC") (class "Default")
      (node (ref "C-10H") (pin "+") (pinfunction "+_+") (pintype "passive"))
      (node (ref "C-10M") (pin "+") (pinfunction "+_+") (pintype "passive"))
      (node (ref "C-10S") (pin "+") (pinfunction "+_+") (pintype "passive"))
      (node (ref "C-H") (pin "+") (pinfunction "+_+") (pintype "passive"))
      (node (ref "C-M") (pin "+") (pinfunction "+_+") (pintype "passive"))
      (node (ref "C-S") (pin "+") (pinfunction "+_+") (pintype "passive"))
      (node (ref "IC-10H") (pin "5") (pinfunction "VCC_5") (pintype "power_in"))
      (node (ref "IC-10M") (pin "5") (pinfunction "VCC_5") (pintype "power_in"))
      (node (ref "IC-10S") (pin "5") (pinfunction "VCC_5") (pintype "power_in"))
      (node (ref "IC-H") (pin "5") (pinfunction "VCC_5") (pintype "power_in"))
      (node (ref "IC-M") (pin "5") (pinfunction "VCC_5") (pintype "power_in"))
      (node (ref "IC-S") (pin "5") (pinfunction "VCC_5") (pintype "power_in"))
      (node (ref "LED1") (pin "C") (pinfunction "C_C") (pintype "passive"))
      (node (ref "LED2") (pin "C") (pinfunction "C_C") (pintype "passive"))
      (node (ref "LED3") (pin "C") (pinfunction "C_C") (pintype "passive"))
      (node (ref "LED4") (pin "C") (pinfunction "C_C") (pintype "passive"))
      (node (ref "LED5") (pin "C") (pinfunction "C_C") (pintype "passive"))
      (node (ref "LED6") (pin "C") (pinfunction "C_C") (pintype "passive"))
      (node (ref "VCC") (pin "1") (pinfunction "1_1") (pintype "passive"))
    )
    (net (code "84") (name "unconnected-(10HOUR-Pad0)") (class "Default")
      (node (ref "10HOUR") (pin "0") (pinfunction "0_0") (pintype "bidirectional"))
    )
    (net (code "85") (name "unconnected-(IC-10HA-0-Pad16)") (class "Default")
      (node (ref "IC-10H") (pin "16") (pinfunction "0_16") (pintype "open_collector"))
    )
    (net (code "86") (name "unconnected-(IC-10HA-3-Pad9)") (class "Default")
      (node (ref "IC-10H") (pin "9") (pinfunction "3_9") (pintype "open_collector"))
    )
    (net (code "87") (name "unconnected-(IC-10HA-4-Pad13)") (class "Default")
      (node (ref "IC-10H") (pin "13") (pinfunction "4_13") (pintype "open_collector"))
    )
    (net (code "88") (name "unconnected-(IC-10HA-5-Pad14)") (class "Default")
      (node (ref "IC-10H") (pin "14") (pinfunction "5_14") (pintype "open_collector"))
    )
    (net (code "89") (name "unconnected-(IC-10HA-6-Pad11)") (class "Default")
      (node (ref "IC-10H") (pin "11") (pinfunction "6_11") (pintype "open_collector"))
    )
    (net (code "90") (name "unconnected-(IC-10HA-7-Pad10)") (class "Default")
      (node (ref "IC-10H") (pin "10") (pinfunction "7_10") (pintype "open_collector"))
    )
    (net (code "91") (name "unconnected-(IC-10HA-8-Pad1)") (class "Default")
      (node (ref "IC-10H") (pin "1") (pinfunction "8_1") (pintype "open_collector"))
    )
    (net (code "92") (name "unconnected-(IC-10HA-9-Pad2)") (class "Default")
      (node (ref "IC-10H") (pin "2") (pinfunction "9_2") (pintype "open_collector"))
    )
    (net (code "93") (name "unconnected-(IC-10MA-6-Pad11)") (class "Default")
      (node (ref "IC-10M") (pin "11") (pinfunction "6_11") (pintype "open_collector"))
    )
    (net (code "94") (name "unconnected-(IC-10MA-7-Pad10)") (class "Default")
      (node (ref "IC-10M") (pin "10") (pinfunction "7_10") (pintype "open_collector"))
    )
    (net (code "95") (name "unconnected-(IC-10MA-8-Pad1)") (class "Default")
      (node (ref "IC-10M") (pin "1") (pinfunction "8_1") (pintype "open_collector"))
    )
    (net (code "96") (name "unconnected-(IC-10MA-9-Pad2)") (class "Default")
      (node (ref "IC-10M") (pin "2") (pinfunction "9_2") (pintype "open_collector"))
    )
    (net (code "97") (name "unconnected-(IC-10SA-6-Pad11)") (class "Default")
      (node (ref "IC-10S") (pin "11") (pinfunction "6_11") (pintype "open_collector"))
    )
    (net (code "98") (name "unconnected-(IC-10SA-7-Pad10)") (class "Default")
      (node (ref "IC-10S") (pin "10") (pinfunction "7_10") (pintype "open_collector"))
    )
    (net (code "99") (name "unconnected-(IC-10SA-8-Pad1)") (class "Default")
      (node (ref "IC-10S") (pin "1") (pinfunction "8_1") (pintype "open_collector"))
    )
    (net (code "100") (name "unconnected-(IC-10SA-9-Pad2)") (class "Default")
      (node (ref "IC-10S") (pin "2") (pinfunction "9_2") (pintype "open_collector"))
    )
  )
)
